# Face_Ant1V0.net
KiCad netlist of a schematic drawn in Altium Designer
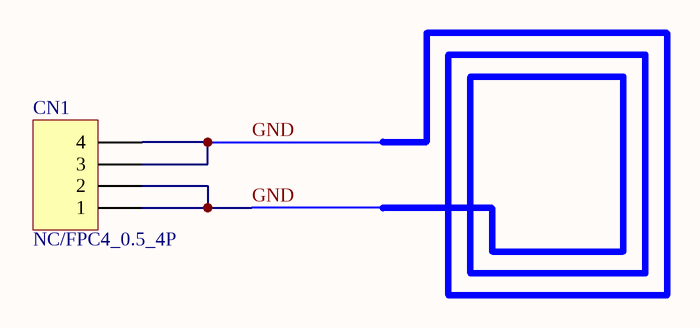
[diagram p0: Face_Ant1V0.SchDoc]

(export (version "E")
  (design (tool "Eeschema 10.0.6"))
  (components
    (comp (ref "CN1")
      (value "NC/FPC4_0.5_4P")
      (footprint "FFC0.5MM-4P")
      (description "FPC4_0.5_4P")
      (fields (field (name "PUBLISHER") "Altium Limited"))
      (libsource (lib "S5X_Ant1V1") (part "Header 1"))
    )
  )
  (nets
    (net (code "1") (name "/GND") (class "Default")
      (node (ref "CN1") (pin "1") (pinfunction "1_1") (pintype "passive"))
      (node (ref "CN1") (pin "2") (pinfunction "2_2") (pintype "passive"))
      (node (ref "CN1") (pin "3") (pinfunction "3_3") (pintype "passive"))
      (node (ref "CN1") (pin "4") (pinfunction "4_4") (pintype "passive"))
    )
  )
)
